# ornithopter001.net
KiCad netlist of a schematic drawn in EAGLE
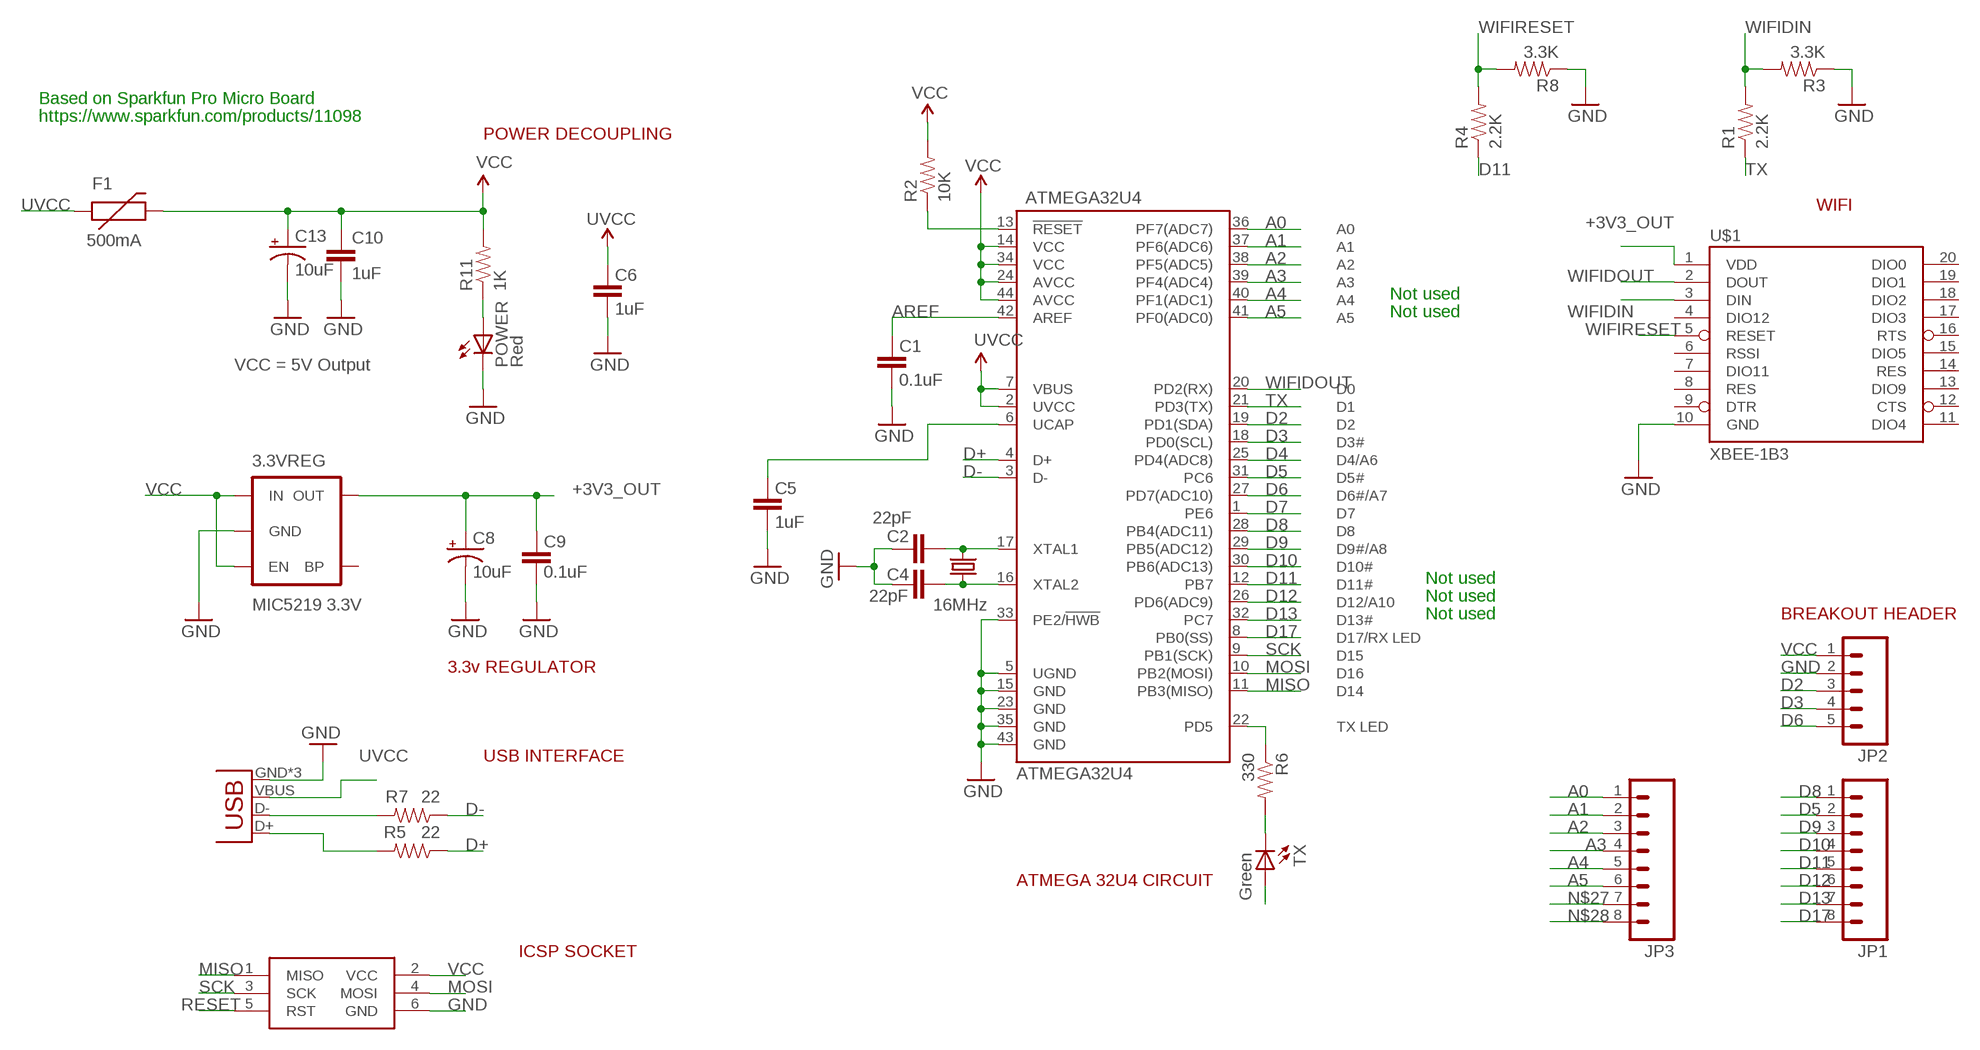
[diagram p0: schematic, sheet 1]

(export (version "E")
  (design (tool "Eeschema 10.0.6"))
  (components
    (comp (ref "3.3VREG")
      (value "MIC5219 3.3V")
      (footprint "eagle-import:SOT23-5")
      (libsource (lib "eagle-import") (part "V_REG_MIC52193.3V"))
    )
    (comp (ref "ATMEGA32U4")
      (value "ATMEGA32U4")
      (footprint "eagle-import:SPARKFUN-DIGITALIC_TQFP44")
      (libsource (lib "eagle-import") (part "ATMEGA32U4TQFP"))
    )
    (comp (ref "C1")
      (value "0.1uF")
      (footprint "eagle-import:0402-CAP")
      (libsource (lib "eagle-import") (part "CAP0402-CAP"))
    )
    (comp (ref "C2")
      (value "22pF")
      (footprint "eagle-import:0402-CAP")
      (libsource (lib "eagle-import") (part "CAP0402-CAP"))
    )
    (comp (ref "C4")
      (value "22pF")
      (footprint "eagle-import:0402-CAP")
      (libsource (lib "eagle-import") (part "CAP0402-CAP"))
    )
    (comp (ref "C5")
      (value "1uF")
      (footprint "eagle-import:0402-CAP")
      (libsource (lib "eagle-import") (part "CAP0402-CAP"))
    )
    (comp (ref "C6")
      (value "1uF")
      (footprint "eagle-import:0402-CAP")
      (libsource (lib "eagle-import") (part "CAP0402-CAP"))
    )
    (comp (ref "C8")
      (value "10uF")
      (footprint "eagle-import:EIA3216")
      (libsource (lib "eagle-import") (part "CAP_POL1206"))
    )
    (comp (ref "C9")
      (value "0.1uF")
      (footprint "eagle-import:0402-CAP")
      (libsource (lib "eagle-import") (part "CAP0402-CAP"))
    )
    (comp (ref "C10")
      (value "1uF")
      (footprint "eagle-import:0402-CAP")
      (libsource (lib "eagle-import") (part "CAP0402-CAP"))
    )
    (comp (ref "C13")
      (value "10uF")
      (footprint "eagle-import:EIA3216")
      (libsource (lib "eagle-import") (part "CAP_POL1206"))
    )
    (comp (ref "F1")
      (value "500mA")
      (footprint "eagle-import:PTC-1206")
      (libsource (lib "eagle-import") (part "PTCSMD"))
    )
    (comp (ref "ISP1")
      (value "AVRISP-6")
      (footprint "eagle-import:AVRISP")
      (libsource (lib "eagle-import") (part "AVRISP-6"))
    )
    (comp (ref "JP1")
      (value "M081X08")
      (footprint "eagle-import:1X08")
      (libsource (lib "eagle-import") (part "M081X08"))
    )
    (comp (ref "JP2")
      (value "M05PTH")
      (footprint "eagle-import:1X05")
      (libsource (lib "eagle-import") (part "M05PTH"))
    )
    (comp (ref "JP3")
      (value "M081X08")
      (footprint "eagle-import:1X08")
      (libsource (lib "eagle-import") (part "M081X08"))
    )
    (comp (ref "POWER")
      (value "Red")
      (footprint "eagle-import:LED-0603")
      (libsource (lib "eagle-import") (part "LED0603"))
    )
    (comp (ref "R1")
      (value "2.2K")
      (footprint "eagle-import:0402-RES")
      (libsource (lib "eagle-import") (part "RESISTOR0402-RES"))
    )
    (comp (ref "R2")
      (value "10K")
      (footprint "eagle-import:0402-RES")
      (libsource (lib "eagle-import") (part "RESISTOR0402-RES"))
    )
    (comp (ref "R3")
      (value "3.3K")
      (footprint "eagle-import:0402-RES")
      (libsource (lib "eagle-import") (part "RESISTOR0402-RES"))
    )
    (comp (ref "R4")
      (value "2.2K")
      (footprint "eagle-import:0402-RES")
      (libsource (lib "eagle-import") (part "RESISTOR0402-RES"))
    )
    (comp (ref "R5")
      (value "22")
      (footprint "eagle-import:0402-RES")
      (libsource (lib "eagle-import") (part "RESISTOR0402-RES"))
    )
    (comp (ref "R6")
      (value "330")
      (footprint "eagle-import:0402-RES")
      (libsource (lib "eagle-import") (part "RESISTOR0402-RES"))
    )
    (comp (ref "R7")
      (value "22")
      (footprint "eagle-import:0402-RES")
      (libsource (lib "eagle-import") (part "RESISTOR0402-RES"))
    )
    (comp (ref "R8")
      (value "3.3K")
      (footprint "eagle-import:0402-RES")
      (libsource (lib "eagle-import") (part "RESISTOR0402-RES"))
    )
    (comp (ref "R11")
      (value "1K")
      (footprint "eagle-import:0402-RES")
      (libsource (lib "eagle-import") (part "RESISTOR0402-RES"))
    )
    (comp (ref "TX")
      (value "Green")
      (footprint "eagle-import:LED-0603")
      (libsource (lib "eagle-import") (part "LED0603"))
    )
    (comp (ref "U$1")
      (value "XBEE-1B3")
      (footprint "eagle-import:XBEE-SMD")
      (libsource (lib "eagle-import") (part "XBEE-1B3"))
    )
    (comp (ref "X2")
      (value "USB-MICROB")
      (footprint "eagle-import:USB-MICROB")
      (libsource (lib "eagle-import") (part "USB-MICROB"))
    )
    (comp (ref "Y1")
      (value "16MHz")
      (footprint "eagle-import:CRYSTAL-SMD-5X3")
      (libsource (lib "eagle-import") (part "CRYSTAL5X3"))
    )
  )
  (nets
    (net (code "1") (name "/+3V3_OUT") (class "Default")
      (node (ref "3.3VREG") (pin "5") (pinfunction "OUT_5") (pintype "passive"))
      (node (ref "C8") (pin "A") (pinfunction "+_A") (pintype "passive"))
      (node (ref "C9") (pin "2") (pinfunction "2_2") (pintype "passive"))
      (node (ref "U$1") (pin "1") (pinfunction "VDD_1") (pintype "power_in"))
    )
    (net (code "2") (name "/A0") (class "Default")
      (node (ref "ATMEGA32U4") (pin "36") (pinfunction "PF7(ADC7)_36") (pintype "bidirectional"))
      (node (ref "JP3") (pin "1") (pinfunction "1_1") (pintype "passive"))
    )
    (net (code "3") (name "/A1") (class "Default")
      (node (ref "ATMEGA32U4") (pin "37") (pinfunction "PF6(ADC6)_37") (pintype "bidirectional"))
      (node (ref "JP3") (pin "2") (pinfunction "2_2") (pintype "passive"))
    )
    (net (code "4") (name "/A2") (class "Default")
      (node (ref "ATMEGA32U4") (pin "38") (pinfunction "PF5(ADC5)_38") (pintype "bidirectional"))
      (node (ref "JP3") (pin "3") (pinfunction "3_3") (pintype "passive"))
    )
    (net (code "5") (name "/A3") (class "Default")
      (node (ref "ATMEGA32U4") (pin "39") (pinfunction "PF4(ADC4)_39") (pintype "bidirectional"))
      (node (ref "JP3") (pin "4") (pinfunction "4_4") (pintype "passive"))
    )
    (net (code "6") (name "/A4") (class "Default")
      (node (ref "ATMEGA32U4") (pin "40") (pinfunction "PF1(ADC1)_40") (pintype "bidirectional"))
      (node (ref "JP3") (pin "5") (pinfunction "5_5") (pintype "passive"))
    )
    (net (code "7") (name "/A5") (class "Default")
      (node (ref "ATMEGA32U4") (pin "41") (pinfunction "PF0(ADC0)_41") (pintype "bidirectional"))
      (node (ref "JP3") (pin "6") (pinfunction "6_6") (pintype "passive"))
    )
    (net (code "8") (name "/AREF") (class "Default")
      (node (ref "ATMEGA32U4") (pin "42") (pinfunction "AREF_42") (pintype "bidirectional"))
      (node (ref "C1") (pin "2") (pinfunction "2_2") (pintype "passive"))
    )
    (net (code "9") (name "/D+") (class "Default")
      (node (ref "ATMEGA32U4") (pin "4") (pinfunction "D+_4") (pintype "bidirectional"))
      (node (ref "R5") (pin "1") (pinfunction "1_1") (pintype "passive"))
    )
    (net (code "10") (name "/D-") (class "Default")
      (node (ref "ATMEGA32U4") (pin "3") (pinfunction "D-_3") (pintype "bidirectional"))
      (node (ref "R7") (pin "1") (pinfunction "1_1") (pintype "passive"))
    )
    (net (code "11") (name "/D2") (class "Default")
      (node (ref "ATMEGA32U4") (pin "19") (pinfunction "PD1(SDA)_19") (pintype "bidirectional"))
      (node (ref "JP2") (pin "3") (pinfunction "3_3") (pintype "passive"))
    )
    (net (code "12") (name "/D3") (class "Default")
      (node (ref "ATMEGA32U4") (pin "18") (pinfunction "PD0(SCL)_18") (pintype "bidirectional"))
      (node (ref "JP2") (pin "4") (pinfunction "4_4") (pintype "passive"))
    )
    (net (code "13") (name "/D4") (class "Default")
      (node (ref "ATMEGA32U4") (pin "25") (pinfunction "PD4(ADC8)_25") (pintype "bidirectional"))
    )
    (net (code "14") (name "/D5") (class "Default")
      (node (ref "ATMEGA32U4") (pin "31") (pinfunction "PC6_31") (pintype "bidirectional"))
      (node (ref "JP1") (pin "2") (pinfunction "2_2") (pintype "passive"))
    )
    (net (code "15") (name "/D6") (class "Default")
      (node (ref "ATMEGA32U4") (pin "27") (pinfunction "PD7(ADC10)_27") (pintype "bidirectional"))
      (node (ref "JP2") (pin "5") (pinfunction "5_5") (pintype "passive"))
    )
    (net (code "16") (name "/D7") (class "Default")
      (node (ref "ATMEGA32U4") (pin "1") (pinfunction "PE6_1") (pintype "bidirectional"))
    )
    (net (code "17") (name "/D8") (class "Default")
      (node (ref "ATMEGA32U4") (pin "28") (pinfunction "PB4(ADC11)_28") (pintype "bidirectional"))
      (node (ref "JP1") (pin "1") (pinfunction "1_1") (pintype "passive"))
    )
    (net (code "18") (name "/D9") (class "Default")
      (node (ref "ATMEGA32U4") (pin "29") (pinfunction "PB5(ADC12)_29") (pintype "bidirectional"))
      (node (ref "JP1") (pin "3") (pinfunction "3_3") (pintype "passive"))
    )
    (net (code "19") (name "/D10") (class "Default")
      (node (ref "ATMEGA32U4") (pin "30") (pinfunction "PB6(ADC13)_30") (pintype "bidirectional"))
      (node (ref "JP1") (pin "4") (pinfunction "4_4") (pintype "passive"))
    )
    (net (code "20") (name "/D11") (class "Default")
      (node (ref "ATMEGA32U4") (pin "12") (pinfunction "PB7_12") (pintype "bidirectional"))
      (node (ref "JP1") (pin "5") (pinfunction "5_5") (pintype "passive"))
      (node (ref "R4") (pin "1") (pinfunction "1_1") (pintype "passive"))
    )
    (net (code "21") (name "/D12") (class "Default")
      (node (ref "ATMEGA32U4") (pin "26") (pinfunction "PD6(ADC9)_26") (pintype "bidirectional"))
      (node (ref "JP1") (pin "6") (pinfunction "6_6") (pintype "passive"))
    )
    (net (code "22") (name "/D13") (class "Default")
      (node (ref "ATMEGA32U4") (pin "32") (pinfunction "PC7_32") (pintype "bidirectional"))
      (node (ref "JP1") (pin "7") (pinfunction "7_7") (pintype "passive"))
    )
    (net (code "23") (name "/D17") (class "Default")
      (node (ref "ATMEGA32U4") (pin "8") (pinfunction "PB0(SS)_8") (pintype "bidirectional"))
      (node (ref "JP1") (pin "8") (pinfunction "8_8") (pintype "passive"))
    )
    (net (code "24") (name "/MISO") (class "Default")
      (node (ref "ATMEGA32U4") (pin "11") (pinfunction "PB3(MISO)_11") (pintype "bidirectional"))
      (node (ref "ISP1") (pin "1") (pinfunction "MISO_1") (pintype "input"))
    )
    (net (code "25") (name "/MOSI") (class "Default")
      (node (ref "ATMEGA32U4") (pin "10") (pinfunction "PB2(MOSI)_10") (pintype "bidirectional"))
      (node (ref "ISP1") (pin "4") (pinfunction "MOSI_4") (pintype "output"))
    )
    (net (code "26") (name "/N$27") (class "Default")
      (node (ref "JP3") (pin "7") (pinfunction "7_7") (pintype "passive"))
    )
    (net (code "27") (name "/N$28") (class "Default")
      (node (ref "JP3") (pin "8") (pinfunction "8_8") (pintype "passive"))
    )
    (net (code "28") (name "/RESET") (class "Default")
      (node (ref "ATMEGA32U4") (pin "13") (pinfunction "~{RESET}_13") (pintype "bidirectional"))
      (node (ref "ISP1") (pin "5") (pinfunction "RST_5") (pintype "output"))
      (node (ref "R2") (pin "1") (pinfunction "1_1") (pintype "passive"))
    )
    (net (code "29") (name "/SCK") (class "Default")
      (node (ref "ATMEGA32U4") (pin "9") (pinfunction "PB1(SCK)_9") (pintype "bidirectional"))
      (node (ref "ISP1") (pin "3") (pinfunction "SCK_3") (pintype "output"))
    )
    (net (code "30") (name "/TX") (class "Default")
      (node (ref "ATMEGA32U4") (pin "21") (pinfunction "PD3(TX)_21") (pintype "bidirectional"))
      (node (ref "R1") (pin "1") (pinfunction "1_1") (pintype "passive"))
    )
    (net (code "31") (name "/WIFIDIN") (class "Default")
      (node (ref "R1") (pin "2") (pinfunction "2_2") (pintype "passive"))
      (node (ref "R3") (pin "2") (pinfunction "2_2") (pintype "passive"))
      (node (ref "U$1") (pin "3") (pinfunction "DIN_3") (pintype "input"))
    )
    (net (code "32") (name "/WIFIDOUT") (class "Default")
      (node (ref "ATMEGA32U4") (pin "20") (pinfunction "PD2(RX)_20") (pintype "bidirectional"))
      (node (ref "U$1") (pin "2") (pinfunction "DOUT_2") (pintype "output"))
    )
    (net (code "33") (name "/WIFIRESET") (class "Default")
      (node (ref "R4") (pin "2") (pinfunction "2_2") (pintype "passive"))
      (node (ref "R8") (pin "2") (pinfunction "2_2") (pintype "passive"))
      (node (ref "U$1") (pin "5") (pinfunction "RESET_5") (pintype "input"))
    )
    (net (code "34") (name "GND") (class "Default")
      (node (ref "3.3VREG") (pin "2") (pinfunction "GND_2") (pintype "input"))
      (node (ref "ATMEGA32U4") (pin "15") (pinfunction "GND_15") (pintype "bidirectional"))
      (node (ref "ATMEGA32U4") (pin "23") (pinfunction "GND_23") (pintype "bidirectional"))
      (node (ref "ATMEGA32U4") (pin "33") (pinfunction "PE2/~{HWB}_33") (pintype "bidirectional"))
      (node (ref "ATMEGA32U4") (pin "35") (pinfunction "GND_35") (pintype "bidirectional"))
      (node (ref "ATMEGA32U4") (pin "43") (pinfunction "GND_43") (pintype "bidirectional"))
      (node (ref "ATMEGA32U4") (pin "5") (pinfunction "UGND_5") (pintype "bidirectional"))
      (node (ref "C1") (pin "1") (pinfunction "1_1") (pintype "passive"))
      (node (ref "C10") (pin "2") (pinfunction "2_2") (pintype "passive"))
      (node (ref "C13") (pin "C") (pinfunction "-_C") (pintype "passive"))
      (node (ref "C2") (pin "2") (pinfunction "2_2") (pintype "passive"))
      (node (ref "C4") (pin "2") (pinfunction "2_2") (pintype "passive"))
      (node (ref "C5") (pin "1") (pinfunction "1_1") (pintype "passive"))
      (node (ref "C6") (pin "1") (pinfunction "1_1") (pintype "passive"))
      (node (ref "C8") (pin "C") (pinfunction "-_C") (pintype "passive"))
      (node (ref "C9") (pin "1") (pinfunction "1_1") (pintype "passive"))
      (node (ref "ISP1") (pin "6") (pinfunction "GND_6") (pintype "power_in"))
      (node (ref "JP2") (pin "2") (pinfunction "2_2") (pintype "passive"))
      (node (ref "POWER") (pin "C") (pinfunction "C_C") (pintype "passive"))
      (node (ref "R3") (pin "1") (pinfunction "1_1") (pintype "passive"))
      (node (ref "R8") (pin "1") (pinfunction "1_1") (pintype "passive"))
      (node (ref "U$1") (pin "10") (pinfunction "GND_10") (pintype "power_in"))
      (node (ref "X2") (pin "GND") (pinfunction "GND_GND") (pintype "bidirectional"))
      (node (ref "X2") (pin "MT1") (pinfunction "GND_MT1") (pintype "bidirectional"))
      (node (ref "X2") (pin "MT2") (pinfunction "GND_MT2") (pintype "bidirectional"))
    )
    (net (code "35") (name "Net-(ATMEGA32U4-PD5)") (class "Default")
      (node (ref "ATMEGA32U4") (pin "22") (pinfunction "PD5_22") (pintype "bidirectional"))
      (node (ref "R6") (pin "1") (pinfunction "1_1") (pintype "passive"))
    )
    (net (code "36") (name "Net-(ATMEGA32U4-UCAP)") (class "Default")
      (node (ref "ATMEGA32U4") (pin "6") (pinfunction "UCAP_6") (pintype "bidirectional"))
      (node (ref "C5") (pin "2") (pinfunction "2_2") (pintype "passive"))
    )
    (net (code "37") (name "Net-(ATMEGA32U4-XTAL1)") (class "Default")
      (node (ref "ATMEGA32U4") (pin "17") (pinfunction "XTAL1_17") (pintype "bidirectional"))
      (node (ref "C2") (pin "1") (pinfunction "1_1") (pintype "passive"))
      (node (ref "Y1") (pin "3") (pinfunction "2_3") (pintype "passive"))
    )
    (net (code "38") (name "Net-(ATMEGA32U4-XTAL2)") (class "Default")
      (node (ref "ATMEGA32U4") (pin "16") (pinfunction "XTAL2_16") (pintype "bidirectional"))
      (node (ref "C4") (pin "1") (pinfunction "1_1") (pintype "passive"))
      (node (ref "Y1") (pin "1") (pinfunction "1_1") (pintype "passive"))
    )
    (net (code "39") (name "Net-(POWER-PadA)") (class "Default")
      (node (ref "POWER") (pin "A") (pinfunction "A_A") (pintype "passive"))
      (node (ref "R11") (pin "1") (pinfunction "1_1") (pintype "passive"))
    )
    (net (code "40") (name "Net-(R5-Pad2)") (class "Default")
      (node (ref "R5") (pin "2") (pinfunction "2_2") (pintype "passive"))
      (node (ref "X2") (pin "D+") (pinfunction "D+_D+") (pintype "bidirectional"))
    )
    (net (code "41") (name "Net-(R6-Pad2)") (class "Default")
      (node (ref "R6") (pin "2") (pinfunction "2_2") (pintype "passive"))
      (node (ref "TX") (pin "C") (pinfunction "C_C") (pintype "passive"))
    )
    (net (code "42") (name "Net-(R7-Pad2)") (class "Default")
      (node (ref "R7") (pin "2") (pinfunction "2_2") (pintype "passive"))
      (node (ref "X2") (pin "D-") (pinfunction "D-_D-") (pintype "bidirectional"))
    )
    (net (code "43") (name "UVCC") (class "Default")
      (node (ref "ATMEGA32U4") (pin "2") (pinfunction "UVCC_2") (pintype "bidirectional"))
      (node (ref "ATMEGA32U4") (pin "7") (pinfunction "VBUS_7") (pintype "bidirectional"))
      (node (ref "C6") (pin "2") (pinfunction "2_2") (pintype "passive"))
      (node (ref "F1") (pin "1") (pinfunction "1_1") (pintype "bidirectional"))
      (node (ref "X2") (pin "VBUS") (pinfunction "VBUS_VBUS") (pintype "bidirectional"))
    )
    (net (code "44") (name "VCC") (class "Default")
      (node (ref "3.3VREG") (pin "1") (pinfunction "IN_1") (pintype "input"))
      (node (ref "3.3VREG") (pin "3") (pinfunction "EN_3") (pintype "input"))
      (node (ref "ATMEGA32U4") (pin "14") (pinfunction "VCC_14") (pintype "bidirectional"))
      (node (ref "ATMEGA32U4") (pin "24") (pinfunction "AVCC_24") (pintype "bidirectional"))
      (node (ref "ATMEGA32U4") (pin "34") (pinfunction "VCC_34") (pintype "bidirectional"))
      (node (ref "ATMEGA32U4") (pin "44") (pinfunction "AVCC_44") (pintype "bidirectional"))
      (node (ref "C10") (pin "1") (pinfunction "1_1") (pintype "passive"))
      (node (ref "C13") (pin "A") (pinfunction "+_A") (pintype "passive"))
      (node (ref "F1") (pin "2") (pinfunction "2_2") (pintype "bidirectional"))
      (node (ref "ISP1") (pin "2") (pinfunction "VCC_2") (pintype "power_in"))
      (node (ref "JP2") (pin "1") (pinfunction "1_1") (pintype "passive"))
      (node (ref "R11") (pin "2") (pinfunction "2_2") (pintype "passive"))
      (node (ref "R2") (pin "2") (pinfunction "2_2") (pintype "passive"))
      (node (ref "TX") (pin "A") (pinfunction "A_A") (pintype "passive"))
    )
    (net (code "45") (name "unconnected-(3.3VREG-BP-Pad4)") (class "Default")
      (node (ref "3.3VREG") (pin "4") (pinfunction "BP_4") (pintype "input"))
    )
    (net (code "46") (name "unconnected-(U$1-CTS-Pad12)") (class "Default")
      (node (ref "U$1") (pin "12") (pinfunction "CTS_12") (pintype "output"))
    )
    (net (code "47") (name "unconnected-(U$1-DIO0-Pad20)") (class "Default")
      (node (ref "U$1") (pin "20") (pinfunction "DIO0_20") (pintype "bidirectional"))
    )
    (net (code "48") (name "unconnected-(U$1-DIO1-Pad19)") (class "Default")
      (node (ref "U$1") (pin "19") (pinfunction "DIO1_19") (pintype "bidirectional"))
    )
    (net (code "49") (name "unconnected-(U$1-DIO2-Pad18)") (class "Default")
      (node (ref "U$1") (pin "18") (pinfunction "DIO2_18") (pintype "bidirectional"))
    )
    (net (code "50") (name "unconnected-(U$1-DIO3-Pad17)") (class "Default")
      (node (ref "U$1") (pin "17") (pinfunction "DIO3_17") (pintype "bidirectional"))
    )
    (net (code "51") (name "unconnected-(U$1-DIO4-Pad11)") (class "Default")
      (node (ref "U$1") (pin "11") (pinfunction "DIO4_11") (pintype "bidirectional"))
    )
    (net (code "52") (name "unconnected-(U$1-DIO5-Pad15)") (class "Default")
      (node (ref "U$1") (pin "15") (pinfunction "DIO5_15") (pintype "bidirectional"))
    )
    (net (code "53") (name "unconnected-(U$1-DIO9-Pad13)") (class "Default")
      (node (ref "U$1") (pin "13") (pinfunction "DIO9_13") (pintype "bidirectional"))
    )
    (net (code "54") (name "unconnected-(U$1-DIO11-Pad7)") (class "Default")
      (node (ref "U$1") (pin "7") (pinfunction "DIO11_7") (pintype "bidirectional"))
    )
    (net (code "55") (name "unconnected-(U$1-DIO12-Pad4)") (class "Default")
      (node (ref "U$1") (pin "4") (pinfunction "DIO12_4") (pintype "bidirectional"))
    )
    (net (code "56") (name "unconnected-(U$1-DTR-Pad9)") (class "Default")
      (node (ref "U$1") (pin "9") (pinfunction "DTR_9") (pintype "bidirectional"))
    )
    (net (code "57") (name "unconnected-(U$1-RES-Pad8)") (class "Default")
      (node (ref "U$1") (pin "8") (pinfunction "RES_8") (pintype "bidirectional"))
    )
    (net (code "58") (name "unconnected-(U$1-RES-Pad14)") (class "Default")
      (node (ref "U$1") (pin "14") (pinfunction "RES_14") (pintype "bidirectional"))
    )
    (net (code "59") (name "unconnected-(U$1-RSSI-Pad6)") (class "Default")
      (node (ref "U$1") (pin "6") (pinfunction "RSSI_6") (pintype "bidirectional"))
    )
    (net (code "60") (name "unconnected-(U$1-RTS-Pad16)") (class "Default")
      (node (ref "U$1") (pin "16") (pinfunction "RTS_16") (pintype "input"))
    )
  )
)
